# POWER.net
KiCad netlist of a schematic drawn in Altium Designer
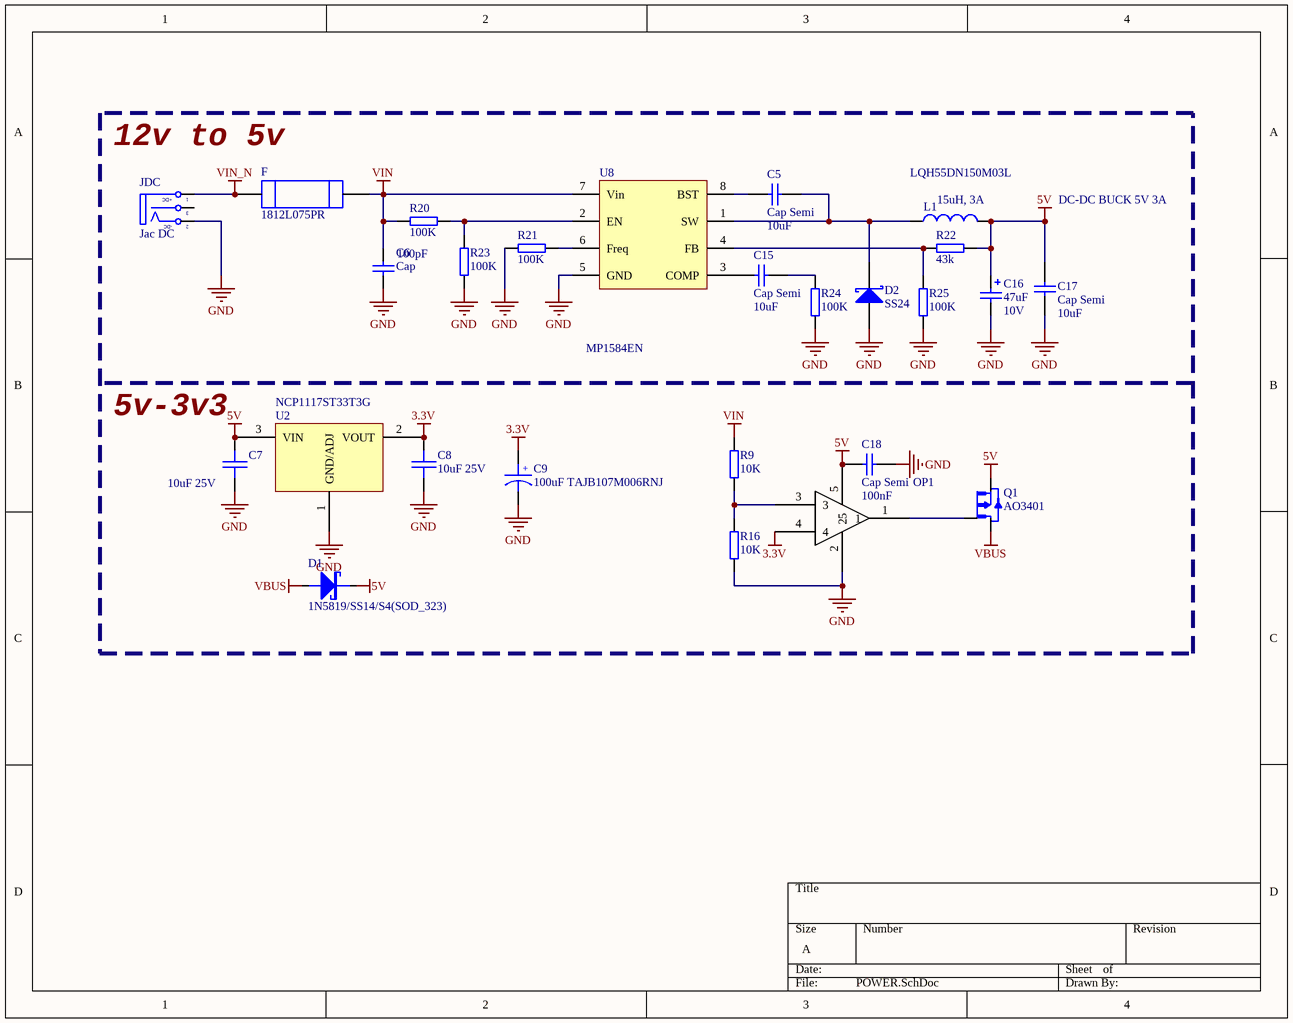
[diagram p0: POWER.SchDoc]

(export (version "E")
  (design (tool "Eeschema 10.0.6"))
  (components
    (comp (ref "C5")
      (value "Cap Semi")
      (footprint "SMT0603")
      (description "CAP SM 0603 X5R 10uF 10%")
      (fields (field (name "TOLERANCE") "±10%") (field (name "ALTIUM_VALUE") "10uF"))
      (libsource (lib "electronpowered") (part "CAP-SM-0603-X5R-10uF"))
    )
    (comp (ref "C6")
      (value "Cap")
      (footprint "CN-SMD-1206")
      (description "Capacitor")
      (fields (field (name "ALTIUM_VALUE") "100pF") (field (name "PUBLISHER") "Altium Limited"))
      (libsource (lib "Miscellaneous Devices") (part "Cap"))
    )
    (comp (ref "C7")
      (value "10uF 25V")
      (footprint "SMT_C_0805")
      (description "Surface mount capacitor 0805")
      (libsource (lib "NODEMCU_DEVKIT_V1.0") (part "SMT_C_0805"))
    )
    (comp (ref "C8")
      (value "10uF 25V")
      (footprint "SMT_C_0805")
      (description "Surface mount capacitor 0805")
      (libsource (lib "NODEMCU_DEVKIT_V1.0") (part "SMT_C_0805"))
    )
    (comp (ref "C9")
      (value "100uF TAJB107M006RNJ")
      (footprint "SMT_C_Tantalum_B")
      (description "Capacitor, SM Tantalum; Body 3.5 x 2.8 mm (LxW typ)")
      (libsource (lib "NODEMCU_DEVKIT_V1.0") (part "SMT_C_Tantalum_B"))
    )
    (comp (ref "C15")
      (value "Cap Semi")
      (footprint "SMT0603")
      (description "CAP SM 0603 X5R 10uF 10%")
      (fields (field (name "TOLERANCE") "±10%") (field (name "ALTIUM_VALUE") "10uF"))
      (libsource (lib "electronpowered") (part "CAP-SM-0603-X5R-10uF"))
    )
    (comp (ref "C16")
      (value "47uF")
      (footprint "Tantal_B")
      (description "Polarized Capacitor (Axial)")
      (fields (field (name "VOLTAGE") "10V") (field (name "PUBLISHER") "Altium Limited"))
      (libsource (lib "mp1584") (part "Cap Pol"))
    )
    (comp (ref "C17")
      (value "Cap Semi")
      (footprint "SMT0603")
      (description "CAP SM 0603 X5R 10uF 10%")
      (fields (field (name "TOLERANCE") "±10%") (field (name "ALTIUM_VALUE") "10uF"))
      (libsource (lib "electronpowered") (part "CAP-SM-0603-X5R-10uF"))
    )
    (comp (ref "C18")
      (value "Cap Semi")
      (footprint "SMT0603")
      (description "CAP SM 0603 X7R 100nF 10%")
      (fields (field (name "TOLERANCE") "±10%") (field (name "ALTIUM_VALUE") "100nF"))
      (libsource (lib "electronpowered") (part "CAP-SM-0603-X7R-100nF"))
    )
    (comp (ref "D1")
      (value "1N5819/SS14/S4(SOD_323)")
      (footprint "SMT_DIODE_SOD_323")
      (description "Surface mount schottky diode SOD-323(0805) Package")
      (libsource (lib "NODEMCU_DEVKIT_V1.0") (part "SMT_DIODE_SCHOTTKY_SOD_323"))
    )
    (comp (ref "D2")
      (value "SS24")
      (footprint "SMB")
      (description "Schottky Diode")
      (fields (field (name "PUBLISHER") "Altium Limited"))
      (libsource (lib "mp1584") (part "D Schottky"))
    )
    (comp (ref "F")
      (value "1812L075PR")
      (footprint "1812")
      (description "Polymeric PTC Resettable Fuse 13.2V 750mA Ih Surface Mount 1812 _4532 Metric_, Concave")
      (fields (field (name "MF") "Littelfuse Inc."))
      (libsource (lib "1812L075PR") (part "1812L075PR"))
    )
    (comp (ref "JDC")
      (value "Jac DC")
      (footprint "DC-IN")
      (description "Jac DC input")
      (libsource (lib "My Library") (part "DCIN"))
    )
    (comp (ref "L1")
      (value "15uH, 3A")
      (footprint "Inductor SMD 6.8*6.8*4.5")
      (fields (field (name "MARKA") "LQH55DN150M03L"))
      (libsource (lib "mp1584") (part "Inductor"))
    )
    (comp (ref "OP1")
      (value "Component_1")
      (footprint "SOT23-5")
      (libsource (lib "mcp601ot") (part "Component_1"))
    )
    (comp (ref "Q1")
      (value "AO3401")
      (footprint "SOT23")
      (description "P-Channel 30V 4A _Ta_ 1.4W _Ta_ Surface Mount SOT-23-3")
      (fields (field (name "MF") "Alpha & Omega Semiconductor"))
      (libsource (lib "AO3401") (part "AO3401"))
    )
    (comp (ref "R9")
      (value "10K")
      (footprint "SMT0603")
      (description "RES SM 0603 10K")
      (fields (field (name "Comment") "Resistor"))
      (libsource (lib "electronpowered") (part "RES-SM-0603-10K"))
    )
    (comp (ref "R16")
      (value "10K")
      (footprint "SMT0603")
      (description "RES SM 0603 10K")
      (fields (field (name "Comment") "Resistor"))
      (libsource (lib "electronpowered") (part "RES-SM-0603-10K"))
    )
    (comp (ref "R20")
      (value "100K")
      (footprint "SMT0603")
      (description "RES SM 0603 100K")
      (fields (field (name "Comment") "Resistor"))
      (libsource (lib "electronpowered") (part "RES-SM-0603-100K"))
    )
    (comp (ref "R21")
      (value "100K")
      (footprint "SMT0603")
      (description "RES SM 0603 100K")
      (fields (field (name "Comment") "Resistor"))
      (libsource (lib "electronpowered") (part "RES-SM-0603-100K"))
    )
    (comp (ref "R22")
      (value "43k")
      (footprint "SMT0603")
      (description "RES SM 0603 100K")
      (fields (field (name "Comment") "Resistor"))
      (libsource (lib "electronpowered") (part "RES-SM-0603-100K"))
    )
    (comp (ref "R23")
      (value "100K")
      (footprint "SMT0603")
      (description "RES SM 0603 100K")
      (fields (field (name "Comment") "Resistor"))
      (libsource (lib "electronpowered") (part "RES-SM-0603-100K"))
    )
    (comp (ref "R24")
      (value "100K")
      (footprint "SMT0603")
      (description "RES SM 0603 100K")
      (fields (field (name "Comment") "Resistor"))
      (libsource (lib "electronpowered") (part "RES-SM-0603-100K"))
    )
    (comp (ref "R25")
      (value "100K")
      (footprint "SMT0603")
      (description "RES SM 0603 100K")
      (fields (field (name "Comment") "Resistor"))
      (libsource (lib "electronpowered") (part "RES-SM-0603-100K"))
    )
    (comp (ref "U2")
      (value "NCP1117ST33T3G")
      (footprint "SOT-223")
      (description "NCP1117, NCV1117. 1.0 A Low-Dropout Positive  Fixed and Adjustable  Voltage Regulators")
      (libsource (lib "NODEMCU_DEVKIT_V1.0") (part "NCP1117"))
    )
    (comp (ref "U8")
      (value "MP1584EN")
      (footprint "SOIC127P600X170-9N")
      (libsource (lib "mp1584") (part "MP1584"))
    )
  )
  (nets
    (net (code "1") (name "3.3V") (class "Default")
      (node (ref "C8") (pin "1") (pinfunction "1_1") (pintype "passive"))
      (node (ref "C9") (pin "1") (pinfunction "1_1") (pintype "passive"))
      (node (ref "OP1") (pin "4") (pinfunction "4_4") (pintype "passive"))
      (node (ref "U2") (pin "2") (pinfunction "VOUT_2") (pintype "passive"))
    )
    (net (code "2") (name "5V") (class "Default")
      (node (ref "C16") (pin "1") (pinfunction "1_1") (pintype "passive"))
      (node (ref "C17") (pin "1") (pinfunction "1_1") (pintype "passive"))
      (node (ref "C18") (pin "1") (pinfunction "1_1") (pintype "passive"))
      (node (ref "C7") (pin "1") (pinfunction "1_1") (pintype "passive"))
      (node (ref "D1") (pin "2") (pinfunction "K_2") (pintype "passive"))
      (node (ref "L1") (pin "2") (pinfunction "2_2") (pintype "passive"))
      (node (ref "OP1") (pin "5") (pinfunction "5_5") (pintype "passive"))
      (node (ref "Q1") (pin "2") (pinfunction "S_2") (pintype "passive"))
      (node (ref "R22") (pin "1") (pinfunction "1_1") (pintype "passive"))
      (node (ref "U2") (pin "3") (pinfunction "VIN_3") (pintype "passive"))
    )
    (net (code "3") (name "GND") (class "Default")
      (node (ref "C16") (pin "2") (pinfunction "2_2") (pintype "passive"))
      (node (ref "C17") (pin "2") (pinfunction "2_2") (pintype "passive"))
      (node (ref "C18") (pin "2") (pinfunction "2_2") (pintype "passive"))
      (node (ref "C6") (pin "2") (pinfunction "2_2") (pintype "passive"))
      (node (ref "C7") (pin "2") (pinfunction "2_2") (pintype "passive"))
      (node (ref "C8") (pin "2") (pinfunction "2_2") (pintype "passive"))
      (node (ref "C9") (pin "2") (pinfunction "2_2") (pintype "passive"))
      (node (ref "D2") (pin "1") (pinfunction "A_1") (pintype "passive"))
      (node (ref "JDC") (pin "2") (pinfunction "TN_2") (pintype "passive"))
      (node (ref "OP1") (pin "2") (pinfunction "2_2") (pintype "passive"))
      (node (ref "R16") (pin "1") (pinfunction "1_1") (pintype "passive"))
      (node (ref "R21") (pin "1") (pinfunction "1_1") (pintype "passive"))
      (node (ref "R23") (pin "2") (pinfunction "2_2") (pintype "passive"))
      (node (ref "R24") (pin "1") (pinfunction "1_1") (pintype "passive"))
      (node (ref "R25") (pin "2") (pinfunction "2_2") (pintype "passive"))
      (node (ref "U2") (pin "1") (pinfunction "GND/ADJ_1") (pintype "passive"))
      (node (ref "U8") (pin "5") (pinfunction "GND_5") (pintype "passive"))
    )
    (net (code "4") (name "Net-(C15-Pad1)") (class "Default")
      (node (ref "C15") (pin "1") (pinfunction "1_1") (pintype "passive"))
      (node (ref "R24") (pin "2") (pinfunction "2_2") (pintype "passive"))
    )
    (net (code "5") (name "Net-(D2-K)") (class "Default")
      (node (ref "C5") (pin "1") (pinfunction "1_1") (pintype "passive"))
      (node (ref "D2") (pin "2") (pinfunction "K_2") (pintype "passive"))
      (node (ref "L1") (pin "1") (pinfunction "1_1") (pintype "passive"))
      (node (ref "U8") (pin "1") (pinfunction "SW_1") (pintype "passive"))
    )
    (net (code "6") (name "Net-(OP1-Pad3)") (class "Default")
      (node (ref "OP1") (pin "3") (pinfunction "3_3") (pintype "passive"))
      (node (ref "R16") (pin "2") (pinfunction "2_2") (pintype "passive"))
      (node (ref "R9") (pin "1") (pinfunction "1_1") (pintype "passive"))
    )
    (net (code "7") (name "Net-(Q1-G)") (class "Default")
      (node (ref "OP1") (pin "1") (pinfunction "1_1") (pintype "passive"))
      (node (ref "Q1") (pin "1") (pinfunction "G_1") (pintype "passive"))
    )
    (net (code "8") (name "Net-(U8-BST)") (class "Default")
      (node (ref "C5") (pin "2") (pinfunction "2_2") (pintype "passive"))
      (node (ref "U8") (pin "8") (pinfunction "BST_8") (pintype "passive"))
    )
    (net (code "9") (name "Net-(U8-COMP)") (class "Default")
      (node (ref "C15") (pin "2") (pinfunction "2_2") (pintype "passive"))
      (node (ref "U8") (pin "3") (pinfunction "COMP_3") (pintype "passive"))
    )
    (net (code "10") (name "Net-(U8-EN)") (class "Default")
      (node (ref "R20") (pin "2") (pinfunction "2_2") (pintype "passive"))
      (node (ref "R23") (pin "1") (pinfunction "1_1") (pintype "passive"))
      (node (ref "U8") (pin "2") (pinfunction "EN_2") (pintype "passive"))
    )
    (net (code "11") (name "Net-(U8-FB)") (class "Default")
      (node (ref "R22") (pin "2") (pinfunction "2_2") (pintype "passive"))
      (node (ref "R25") (pin "1") (pinfunction "1_1") (pintype "passive"))
      (node (ref "U8") (pin "4") (pinfunction "FB_4") (pintype "passive"))
    )
    (net (code "12") (name "Net-(U8-Freq)") (class "Default")
      (node (ref "R21") (pin "2") (pinfunction "2_2") (pintype "passive"))
      (node (ref "U8") (pin "6") (pinfunction "Freq_6") (pintype "passive"))
    )
    (net (code "13") (name "VBUS") (class "Default")
      (node (ref "D1") (pin "1") (pinfunction "A_1") (pintype "passive"))
      (node (ref "Q1") (pin "3") (pinfunction "D_3") (pintype "passive"))
    )
    (net (code "14") (name "VIN") (class "Default")
      (node (ref "C6") (pin "1") (pinfunction "1_1") (pintype "passive"))
      (node (ref "F") (pin "2") (pinfunction "2_2") (pintype "passive"))
      (node (ref "R20") (pin "1") (pinfunction "1_1") (pintype "passive"))
      (node (ref "R9") (pin "2") (pinfunction "2_2") (pintype "passive"))
      (node (ref "U8") (pin "7") (pinfunction "Vin_7") (pintype "passive"))
    )
    (net (code "15") (name "VIN_N") (class "Default")
      (node (ref "F") (pin "1") (pinfunction "1_1") (pintype "passive"))
      (node (ref "JDC") (pin "1") (pinfunction "T_1") (pintype "passive"))
    )
    (net (code "16") (name "unconnected-(JDC-S-Pad3)") (class "Default")
      (node (ref "JDC") (pin "3") (pinfunction "S_3") (pintype "power_in"))
    )
  )
)
